# old_small_line.net
KiCad netlist of a schematic drawn in EAGLE
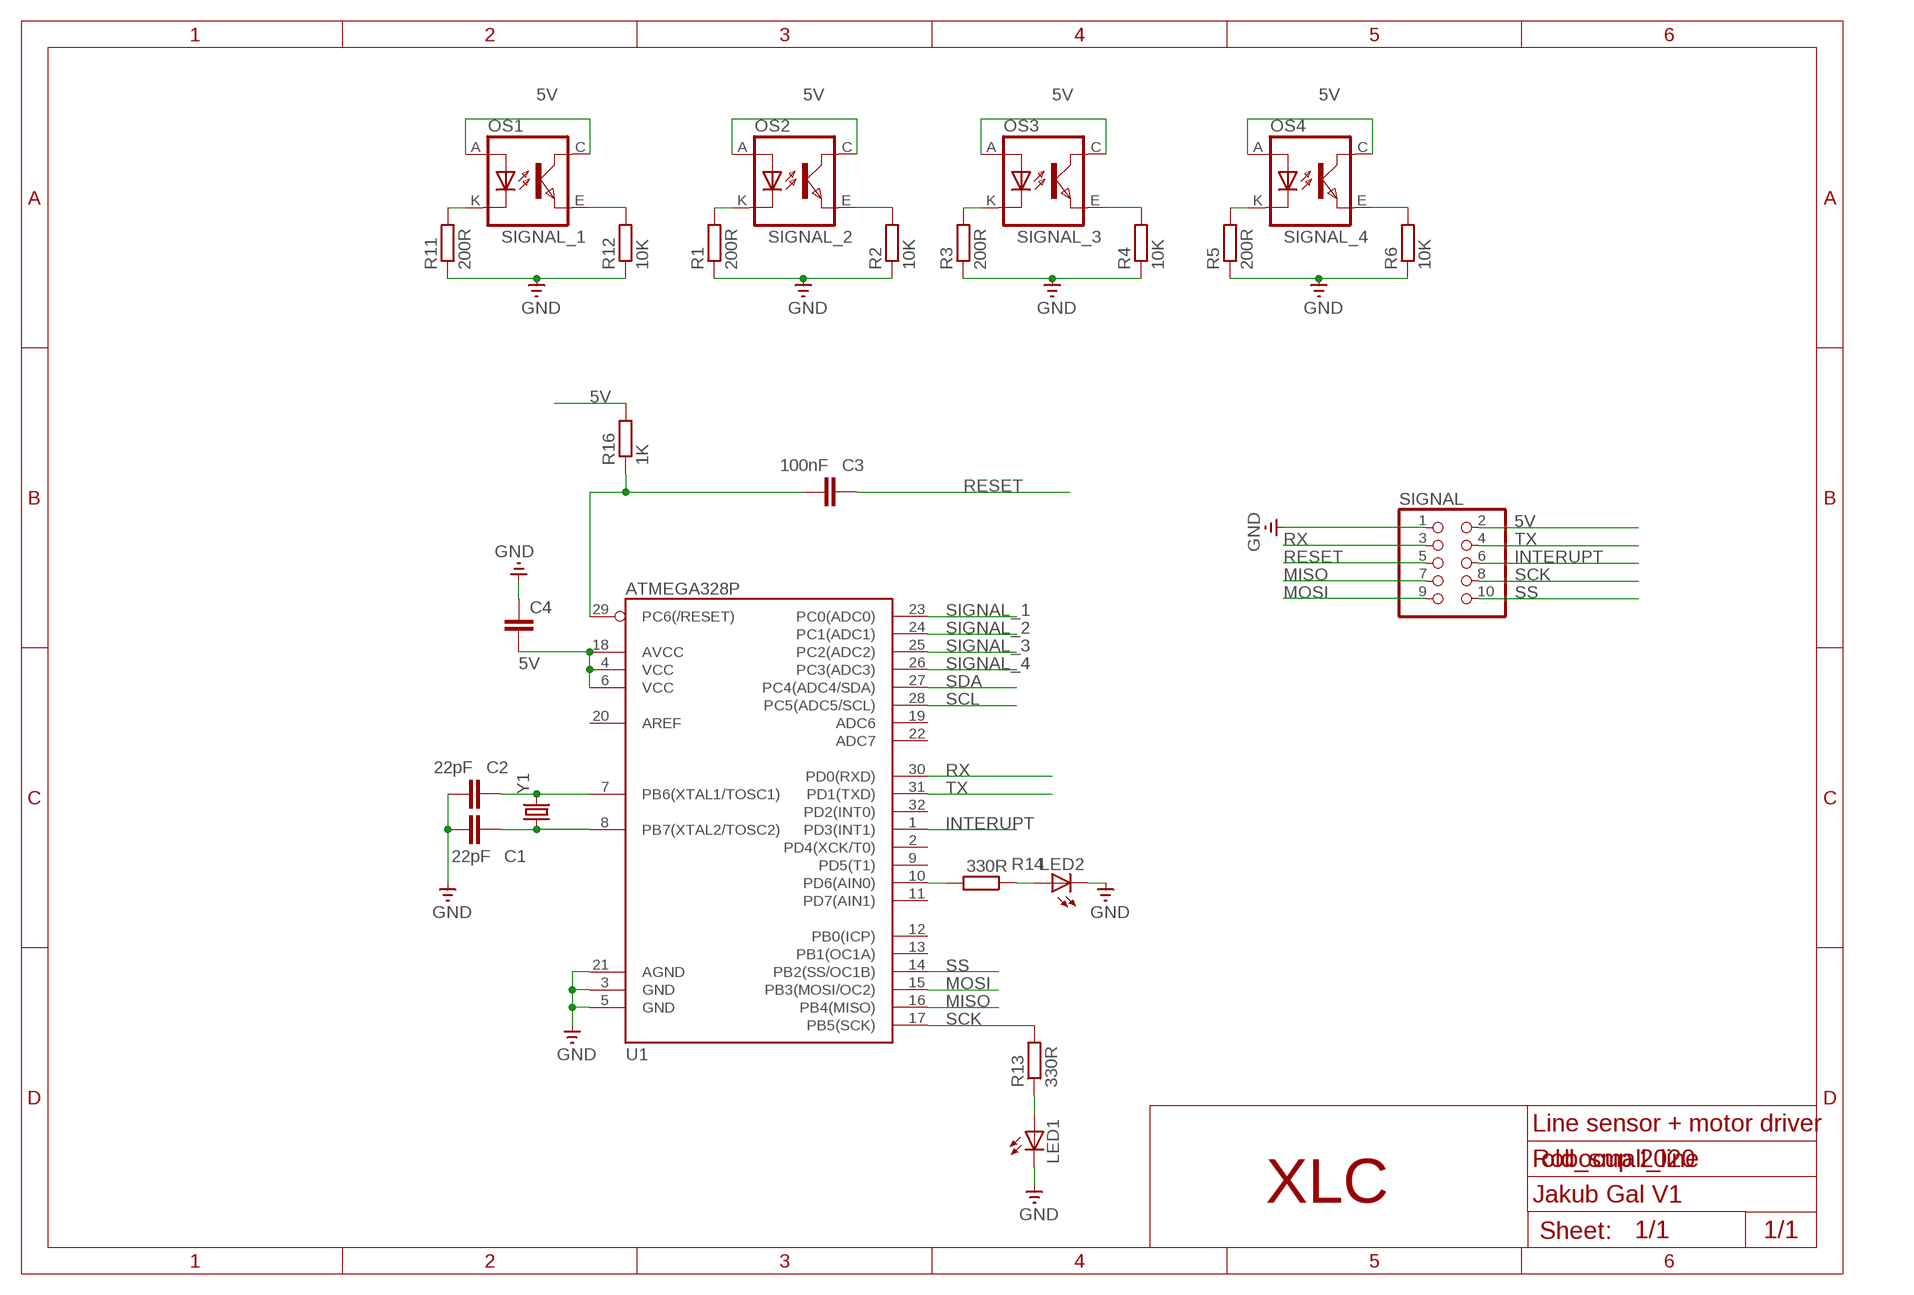
[diagram p0: schematic, sheet 1]

(export (version "E")
  (design (tool "Eeschema 10.0.6"))
  (components
    (comp (ref "C1")
      (value "22pF")
      (footprint "eagle-import:C0603")
      (libsource (lib "eagle-import") (part "rcl@1_C-EUC0603"))
    )
    (comp (ref "C2")
      (value "22pF")
      (footprint "eagle-import:C0603")
      (libsource (lib "eagle-import") (part "rcl@1_C-EUC0603"))
    )
    (comp (ref "C3")
      (value "100nF")
      (footprint "eagle-import:C0603")
      (libsource (lib "eagle-import") (part "rcl@1_C-EUC0603"))
    )
    (comp (ref "C4")
      (value "C-EUC0603")
      (footprint "eagle-import:C0603")
      (libsource (lib "eagle-import") (part "C-EUC0603"))
    )
    (comp (ref "LED1")
      (value "LEDCHIPLED_0603")
      (footprint "eagle-import:CHIPLED_0603")
      (libsource (lib "eagle-import") (part "LEDCHIPLED_0603"))
    )
    (comp (ref "LED2")
      (value "LEDCHIPLED_0603")
      (footprint "eagle-import:CHIPLED_0603")
      (libsource (lib "eagle-import") (part "LEDCHIPLED_0603"))
    )
    (comp (ref "OS1")
      (value "TCRT5000")
      (footprint "eagle-import:TCRT5000")
      (libsource (lib "eagle-import") (part "TCRT5000"))
    )
    (comp (ref "OS2")
      (value "TCRT5000")
      (footprint "eagle-import:TCRT5000")
      (libsource (lib "eagle-import") (part "TCRT5000"))
    )
    (comp (ref "OS3")
      (value "TCRT5000")
      (footprint "eagle-import:TCRT5000")
      (libsource (lib "eagle-import") (part "TCRT5000"))
    )
    (comp (ref "OS4")
      (value "TCRT5000")
      (footprint "eagle-import:TCRT5000")
      (libsource (lib "eagle-import") (part "TCRT5000"))
    )
    (comp (ref "R1")
      (value "200R")
      (footprint "eagle-import:R0603")
      (libsource (lib "eagle-import") (part "R-EU_R0603"))
    )
    (comp (ref "R2")
      (value "10K")
      (footprint "eagle-import:R0603")
      (libsource (lib "eagle-import") (part "R-EU_R0603"))
    )
    (comp (ref "R3")
      (value "200R")
      (footprint "eagle-import:R0603")
      (libsource (lib "eagle-import") (part "R-EU_R0603"))
    )
    (comp (ref "R4")
      (value "10K")
      (footprint "eagle-import:R0603")
      (libsource (lib "eagle-import") (part "R-EU_R0603"))
    )
    (comp (ref "R5")
      (value "200R")
      (footprint "eagle-import:R0603")
      (libsource (lib "eagle-import") (part "R-EU_R0603"))
    )
    (comp (ref "R6")
      (value "10K")
      (footprint "eagle-import:R0603")
      (libsource (lib "eagle-import") (part "R-EU_R0603"))
    )
    (comp (ref "R11")
      (value "200R")
      (footprint "eagle-import:R0603")
      (libsource (lib "eagle-import") (part "R-EU_R0603"))
    )
    (comp (ref "R12")
      (value "10K")
      (footprint "eagle-import:R0603")
      (libsource (lib "eagle-import") (part "R-EU_R0603"))
    )
    (comp (ref "R13")
      (value "330R")
      (footprint "eagle-import:R0603")
      (libsource (lib "eagle-import") (part "R-EU_R0603"))
    )
    (comp (ref "R14")
      (value "330R")
      (footprint "eagle-import:R0603")
      (libsource (lib "eagle-import") (part "R-EU_R0603"))
    )
    (comp (ref "R16")
      (value "1K")
      (footprint "eagle-import:R0603")
      (libsource (lib "eagle-import") (part "R-EU_R0603"))
    )
    (comp (ref "SIGNAL")
      (value "PINHD-2X5IDC")
      (footprint "eagle-import:2X05_IDC")
      (libsource (lib "eagle-import") (part "PINHD-2X5IDC"))
    )
    (comp (ref "U1")
      (value "ATMEGA328P")
      (footprint "eagle-import:TQFP32-08")
      (libsource (lib "eagle-import") (part "ATMEGA328_SMT"))
    )
    (comp (ref "Y1")
      (value "CRYSTALHC49US")
      (footprint "eagle-import:HC49US")
      (libsource (lib "eagle-import") (part "CRYSTALHC49US"))
    )
  )
  (nets
    (net (code "1") (name "/5V") (class "Default")
      (node (ref "C4") (pin "2") (pinfunction "2_2") (pintype "passive"))
      (node (ref "OS1") (pin "A") (pinfunction "ANODE_A") (pintype "passive"))
      (node (ref "OS1") (pin "C") (pinfunction "COLLECTOR_C") (pintype "passive"))
      (node (ref "OS2") (pin "A") (pinfunction "ANODE_A") (pintype "passive"))
      (node (ref "OS2") (pin "C") (pinfunction "COLLECTOR_C") (pintype "passive"))
      (node (ref "OS3") (pin "A") (pinfunction "ANODE_A") (pintype "passive"))
      (node (ref "OS3") (pin "C") (pinfunction "COLLECTOR_C") (pintype "passive"))
      (node (ref "OS4") (pin "A") (pinfunction "ANODE_A") (pintype "passive"))
      (node (ref "OS4") (pin "C") (pinfunction "COLLECTOR_C") (pintype "passive"))
      (node (ref "R16") (pin "2") (pinfunction "2_2") (pintype "passive"))
      (node (ref "SIGNAL") (pin "2") (pinfunction "2_2") (pintype "passive"))
      (node (ref "U1") (pin "18") (pinfunction "AVCC_18") (pintype "bidirectional"))
      (node (ref "U1") (pin "4") (pinfunction "VCC_4") (pintype "bidirectional"))
      (node (ref "U1") (pin "6") (pinfunction "VCC_6") (pintype "bidirectional"))
    )
    (net (code "2") (name "/INTERUPT") (class "Default")
      (node (ref "SIGNAL") (pin "6") (pinfunction "6_6") (pintype "passive"))
      (node (ref "U1") (pin "1") (pinfunction "PD3(INT1)_1") (pintype "bidirectional"))
    )
    (net (code "3") (name "/MISO") (class "Default")
      (node (ref "SIGNAL") (pin "7") (pinfunction "7_7") (pintype "passive"))
      (node (ref "U1") (pin "16") (pinfunction "PB4(MISO)_16") (pintype "bidirectional"))
    )
    (net (code "4") (name "/MOSI") (class "Default")
      (node (ref "SIGNAL") (pin "9") (pinfunction "9_9") (pintype "passive"))
      (node (ref "U1") (pin "15") (pinfunction "PB3(MOSI/OC2)_15") (pintype "bidirectional"))
    )
    (net (code "5") (name "/RESET") (class "Default")
      (node (ref "C3") (pin "2") (pinfunction "2_2") (pintype "passive"))
      (node (ref "SIGNAL") (pin "5") (pinfunction "5_5") (pintype "passive"))
    )
    (net (code "6") (name "/RX") (class "Default")
      (node (ref "SIGNAL") (pin "3") (pinfunction "3_3") (pintype "passive"))
      (node (ref "U1") (pin "30") (pinfunction "PD0(RXD)_30") (pintype "bidirectional"))
    )
    (net (code "7") (name "/SCK") (class "Default")
      (node (ref "R13") (pin "2") (pinfunction "2_2") (pintype "passive"))
      (node (ref "SIGNAL") (pin "8") (pinfunction "8_8") (pintype "passive"))
      (node (ref "U1") (pin "17") (pinfunction "PB5(SCK)_17") (pintype "bidirectional"))
    )
    (net (code "8") (name "/SCL") (class "Default")
      (node (ref "U1") (pin "28") (pinfunction "PC5(ADC5/SCL)_28") (pintype "bidirectional"))
    )
    (net (code "9") (name "/SDA") (class "Default")
      (node (ref "U1") (pin "27") (pinfunction "PC4(ADC4/SDA)_27") (pintype "bidirectional"))
    )
    (net (code "10") (name "/SIGNAL_1") (class "Default")
      (node (ref "OS1") (pin "E") (pinfunction "EMITTER_E") (pintype "passive"))
      (node (ref "R12") (pin "2") (pinfunction "2_2") (pintype "passive"))
      (node (ref "U1") (pin "23") (pinfunction "PC0(ADC0)_23") (pintype "bidirectional"))
    )
    (net (code "11") (name "/SIGNAL_2") (class "Default")
      (node (ref "OS2") (pin "E") (pinfunction "EMITTER_E") (pintype "passive"))
      (node (ref "R2") (pin "2") (pinfunction "2_2") (pintype "passive"))
      (node (ref "U1") (pin "24") (pinfunction "PC1(ADC1)_24") (pintype "bidirectional"))
    )
    (net (code "12") (name "/SIGNAL_3") (class "Default")
      (node (ref "OS3") (pin "E") (pinfunction "EMITTER_E") (pintype "passive"))
      (node (ref "R4") (pin "2") (pinfunction "2_2") (pintype "passive"))
      (node (ref "U1") (pin "25") (pinfunction "PC2(ADC2)_25") (pintype "bidirectional"))
    )
    (net (code "13") (name "/SIGNAL_4") (class "Default")
      (node (ref "OS4") (pin "E") (pinfunction "EMITTER_E") (pintype "passive"))
      (node (ref "R6") (pin "2") (pinfunction "2_2") (pintype "passive"))
      (node (ref "U1") (pin "26") (pinfunction "PC3(ADC3)_26") (pintype "bidirectional"))
    )
    (net (code "14") (name "/SS") (class "Default")
      (node (ref "SIGNAL") (pin "10") (pinfunction "10_10") (pintype "passive"))
      (node (ref "U1") (pin "14") (pinfunction "PB2(SS/OC1B)_14") (pintype "bidirectional"))
    )
    (net (code "15") (name "/TX") (class "Default")
      (node (ref "SIGNAL") (pin "4") (pinfunction "4_4") (pintype "passive"))
      (node (ref "U1") (pin "31") (pinfunction "PD1(TXD)_31") (pintype "bidirectional"))
    )
    (net (code "16") (name "GND") (class "Default")
      (node (ref "C1") (pin "1") (pinfunction "1_1") (pintype "passive"))
      (node (ref "C2") (pin "1") (pinfunction "1_1") (pintype "passive"))
      (node (ref "C4") (pin "1") (pinfunction "1_1") (pintype "passive"))
      (node (ref "LED1") (pin "C") (pinfunction "C_C") (pintype "passive"))
      (node (ref "LED2") (pin "C") (pinfunction "C_C") (pintype "passive"))
      (node (ref "R1") (pin "1") (pinfunction "1_1") (pintype "passive"))
      (node (ref "R11") (pin "1") (pinfunction "1_1") (pintype "passive"))
      (node (ref "R12") (pin "1") (pinfunction "1_1") (pintype "passive"))
      (node (ref "R2") (pin "1") (pinfunction "1_1") (pintype "passive"))
      (node (ref "R3") (pin "1") (pinfunction "1_1") (pintype "passive"))
      (node (ref "R4") (pin "1") (pinfunction "1_1") (pintype "passive"))
      (node (ref "R5") (pin "1") (pinfunction "1_1") (pintype "passive"))
      (node (ref "R6") (pin "1") (pinfunction "1_1") (pintype "passive"))
      (node (ref "SIGNAL") (pin "1") (pinfunction "1_1") (pintype "passive"))
      (node (ref "U1") (pin "21") (pinfunction "AGND_21") (pintype "bidirectional"))
      (node (ref "U1") (pin "3") (pinfunction "GND_3") (pintype "bidirectional"))
      (node (ref "U1") (pin "5") (pinfunction "GND_5") (pintype "bidirectional"))
    )
    (net (code "17") (name "Net-(LED1-PadA)") (class "Default")
      (node (ref "LED1") (pin "A") (pinfunction "A_A") (pintype "passive"))
      (node (ref "R13") (pin "1") (pinfunction "1_1") (pintype "passive"))
    )
    (net (code "18") (name "Net-(LED2-PadA)") (class "Default")
      (node (ref "LED2") (pin "A") (pinfunction "A_A") (pintype "passive"))
      (node (ref "R14") (pin "1") (pinfunction "1_1") (pintype "passive"))
    )
    (net (code "19") (name "Net-(OS1-CATHODE)") (class "Default")
      (node (ref "OS1") (pin "K") (pinfunction "CATHODE_K") (pintype "passive"))
      (node (ref "R11") (pin "2") (pinfunction "2_2") (pintype "passive"))
    )
    (net (code "20") (name "Net-(OS2-CATHODE)") (class "Default")
      (node (ref "OS2") (pin "K") (pinfunction "CATHODE_K") (pintype "passive"))
      (node (ref "R1") (pin "2") (pinfunction "2_2") (pintype "passive"))
    )
    (net (code "21") (name "Net-(OS3-CATHODE)") (class "Default")
      (node (ref "OS3") (pin "K") (pinfunction "CATHODE_K") (pintype "passive"))
      (node (ref "R3") (pin "2") (pinfunction "2_2") (pintype "passive"))
    )
    (net (code "22") (name "Net-(OS4-CATHODE)") (class "Default")
      (node (ref "OS4") (pin "K") (pinfunction "CATHODE_K") (pintype "passive"))
      (node (ref "R5") (pin "2") (pinfunction "2_2") (pintype "passive"))
    )
    (net (code "23") (name "Net-(U1-PB6(XTAL1{slash}TOSC1))") (class "Default")
      (node (ref "C2") (pin "2") (pinfunction "2_2") (pintype "passive"))
      (node (ref "U1") (pin "7") (pinfunction "PB6(XTAL1/TOSC1)_7") (pintype "bidirectional"))
      (node (ref "Y1") (pin "2") (pinfunction "2_2") (pintype "passive"))
    )
    (net (code "24") (name "Net-(U1-PB7(XTAL2{slash}TOSC2))") (class "Default")
      (node (ref "C1") (pin "2") (pinfunction "2_2") (pintype "passive"))
      (node (ref "U1") (pin "8") (pinfunction "PB7(XTAL2/TOSC2)_8") (pintype "bidirectional"))
      (node (ref "Y1") (pin "1") (pinfunction "1_1") (pintype "passive"))
    )
    (net (code "25") (name "Net-(U1-PC6({slash}RESET))") (class "Default")
      (node (ref "C3") (pin "1") (pinfunction "1_1") (pintype "passive"))
      (node (ref "R16") (pin "1") (pinfunction "1_1") (pintype "passive"))
      (node (ref "U1") (pin "29") (pinfunction "PC6(/RESET)_29") (pintype "bidirectional"))
    )
    (net (code "26") (name "Net-(U1-PD6(AIN0))") (class "Default")
      (node (ref "R14") (pin "2") (pinfunction "2_2") (pintype "passive"))
      (node (ref "U1") (pin "10") (pinfunction "PD6(AIN0)_10") (pintype "bidirectional"))
    )
    (net (code "27") (name "unconnected-(U1-ADC6-Pad19)") (class "Default")
      (node (ref "U1") (pin "19") (pinfunction "ADC6_19") (pintype "bidirectional"))
    )
    (net (code "28") (name "unconnected-(U1-ADC7-Pad22)") (class "Default")
      (node (ref "U1") (pin "22") (pinfunction "ADC7_22") (pintype "bidirectional"))
    )
    (net (code "29") (name "unconnected-(U1-AREF-Pad20)") (class "Default")
      (node (ref "U1") (pin "20") (pinfunction "AREF_20") (pintype "bidirectional"))
    )
    (net (code "30") (name "unconnected-(U1-PB0(ICP)-Pad12)") (class "Default")
      (node (ref "U1") (pin "12") (pinfunction "PB0(ICP)_12") (pintype "bidirectional"))
    )
    (net (code "31") (name "unconnected-(U1-PB1(OC1A)-Pad13)") (class "Default")
      (node (ref "U1") (pin "13") (pinfunction "PB1(OC1A)_13") (pintype "bidirectional"))
    )
    (net (code "32") (name "unconnected-(U1-PD2(INT0)-Pad32)") (class "Default")
      (node (ref "U1") (pin "32") (pinfunction "PD2(INT0)_32") (pintype "bidirectional"))
    )
    (net (code "33") (name "unconnected-(U1-PD4(XCK{slash}T0)-Pad2)") (class "Default")
      (node (ref "U1") (pin "2") (pinfunction "PD4(XCK/T0)_2") (pintype "bidirectional"))
    )
    (net (code "34") (name "unconnected-(U1-PD5(T1)-Pad9)") (class "Default")
      (node (ref "U1") (pin "9") (pinfunction "PD5(T1)_9") (pintype "bidirectional"))
    )
    (net (code "35") (name "unconnected-(U1-PD7(AIN1)-Pad11)") (class "Default")
      (node (ref "U1") (pin "11") (pinfunction "PD7(AIN1)_11") (pintype "bidirectional"))
    )
  )
)
